# BattVoltageLevelDetector.net
KiCad netlist of a schematic drawn in Altium Designer
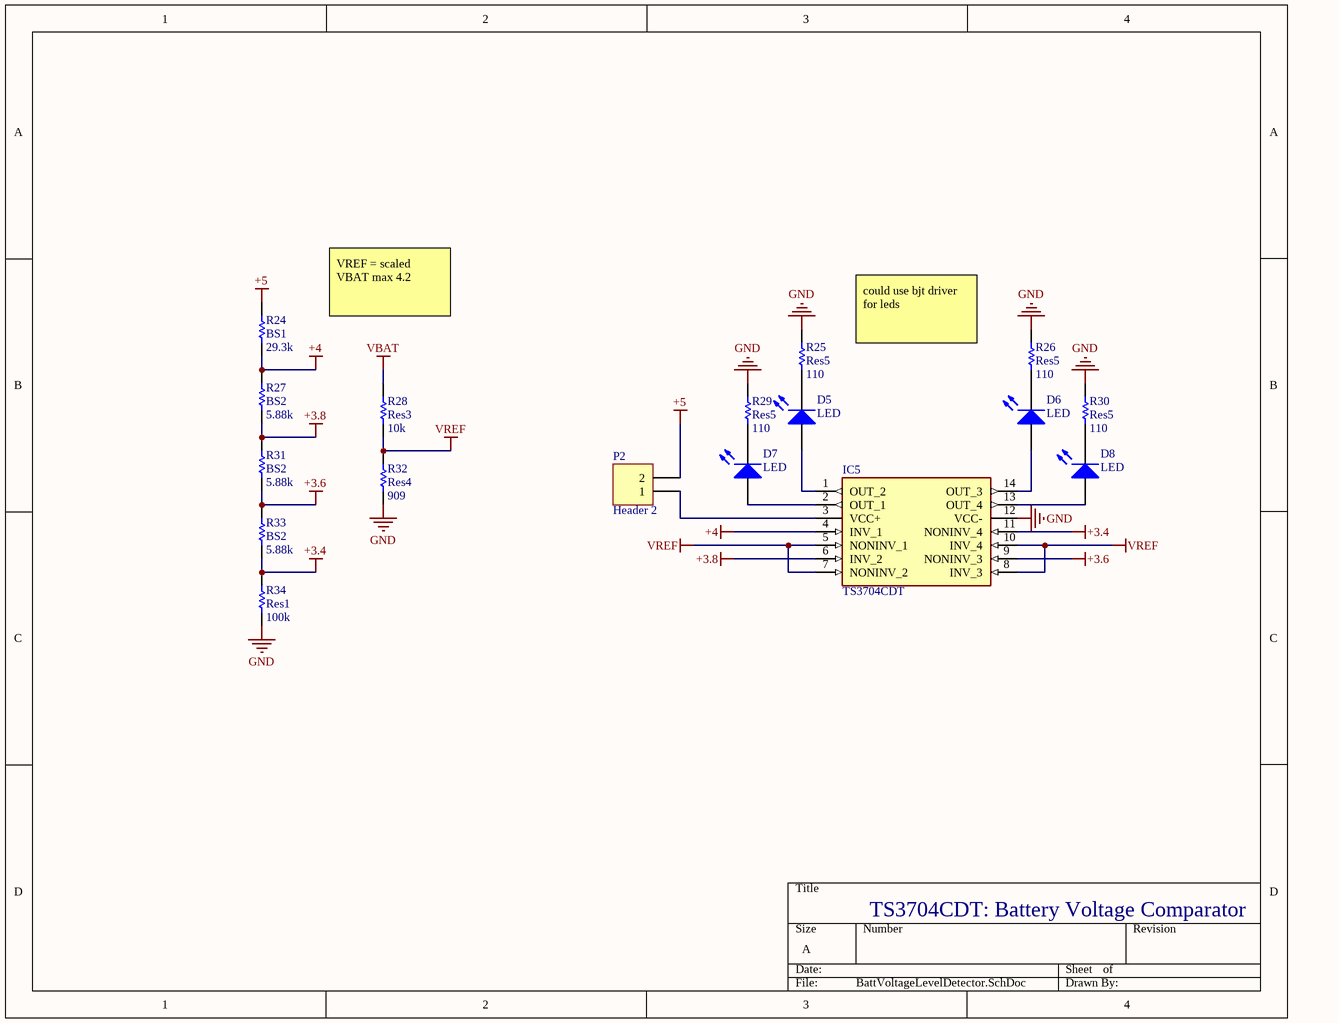
[diagram p0: BattVoltageLevelDetector.SchDoc]

(export (version "E")
  (design (tool "Eeschema 10.0.6"))
  (components
    (comp (ref "D5")
      (value "LED")
      (footprint "0402")
      (description "Typical INFRARED GaAs LED")
      (fields (field (name "PUBLISHER") "Altium Limited"))
      (libsource (lib "Miscellaneous Devices") (part "LED0"))
    )
    (comp (ref "D6")
      (value "LED")
      (footprint "0402")
      (description "Typical INFRARED GaAs LED")
      (fields (field (name "PUBLISHER") "Altium Limited"))
      (libsource (lib "Miscellaneous Devices") (part "LED0"))
    )
    (comp (ref "D7")
      (value "LED")
      (footprint "0402")
      (description "Typical INFRARED GaAs LED")
      (fields (field (name "PUBLISHER") "Altium Limited"))
      (libsource (lib "Miscellaneous Devices") (part "LED0"))
    )
    (comp (ref "D8")
      (value "LED")
      (footprint "0402")
      (description "Typical INFRARED GaAs LED")
      (fields (field (name "PUBLISHER") "Altium Limited"))
      (libsource (lib "Miscellaneous Devices") (part "LED0"))
    )
    (comp (ref "IC5")
      (value "TS3704CDT")
      (footprint "SOIC127P600X175-14N")
      (description "Integrated Circuit")
      (fields (field (name "MOUSER PART NUMBER") "511-TS3704CDT") (field (name "RS PART NUMBER") "8805496P"))
      (libsource (lib "*") (part "TS3704CDT"))
    )
    (comp (ref "P2")
      (value "Header 2")
      (footprint "HDR1X2")
      (description "Header, 2-Pin")
      (fields (field (name "PUBLISHER") "Altium Limited"))
      (libsource (lib "Miscellaneous Connectors") (part "Header 2"))
    )
    (comp (ref "R24")
      (value "BS1")
      (footprint "0402")
      (description "Resistor")
      (fields (field (name "ALTIUM_VALUE") "29.3k") (field (name "PUBLISHER") "Altium Limited"))
      (libsource (lib "Miscellaneous Devices") (part "Res1"))
    )
    (comp (ref "R25")
      (value "Res5")
      (footprint "0402")
      (description "Resistor")
      (fields (field (name "ALTIUM_VALUE") "110") (field (name "PUBLISHER") "Altium Limited"))
      (libsource (lib "Miscellaneous Devices") (part "Res1"))
    )
    (comp (ref "R26")
      (value "Res5")
      (footprint "0402")
      (description "Resistor")
      (fields (field (name "ALTIUM_VALUE") "110") (field (name "PUBLISHER") "Altium Limited"))
      (libsource (lib "Miscellaneous Devices") (part "Res1"))
    )
    (comp (ref "R27")
      (value "BS2")
      (footprint "0402")
      (description "Resistor")
      (fields (field (name "ALTIUM_VALUE") "5.88k") (field (name "PUBLISHER") "Altium Limited"))
      (libsource (lib "Miscellaneous Devices") (part "Res1"))
    )
    (comp (ref "R28")
      (value "Res3")
      (footprint "0402")
      (description "Resistor")
      (fields (field (name "ALTIUM_VALUE") "10k") (field (name "PUBLISHER") "Altium Limited"))
      (libsource (lib "Miscellaneous Devices") (part "Res1"))
    )
    (comp (ref "R29")
      (value "Res5")
      (footprint "0402")
      (description "Resistor")
      (fields (field (name "ALTIUM_VALUE") "110") (field (name "PUBLISHER") "Altium Limited"))
      (libsource (lib "Miscellaneous Devices") (part "Res1"))
    )
    (comp (ref "R30")
      (value "Res5")
      (footprint "0402")
      (description "Resistor")
      (fields (field (name "ALTIUM_VALUE") "110") (field (name "PUBLISHER") "Altium Limited"))
      (libsource (lib "Miscellaneous Devices") (part "Res1"))
    )
    (comp (ref "R31")
      (value "BS2")
      (footprint "0402")
      (description "Resistor")
      (fields (field (name "ALTIUM_VALUE") "5.88k") (field (name "PUBLISHER") "Altium Limited"))
      (libsource (lib "Miscellaneous Devices") (part "Res1"))
    )
    (comp (ref "R32")
      (value "Res4")
      (footprint "0402")
      (description "Resistor")
      (fields (field (name "ALTIUM_VALUE") "909") (field (name "PUBLISHER") "Altium Limited"))
      (libsource (lib "Miscellaneous Devices") (part "Res1"))
    )
    (comp (ref "R33")
      (value "BS2")
      (footprint "0402")
      (description "Resistor")
      (fields (field (name "ALTIUM_VALUE") "5.88k") (field (name "PUBLISHER") "Altium Limited"))
      (libsource (lib "Miscellaneous Devices") (part "Res1"))
    )
    (comp (ref "R34")
      (value "Res1")
      (footprint "0402")
      (description "Resistor")
      (fields (field (name "ALTIUM_VALUE") "100k") (field (name "PUBLISHER") "Altium Limited"))
      (libsource (lib "Miscellaneous Devices") (part "Res1"))
    )
  )
  (nets
    (net (code "1") (name "+3.4") (class "Default")
      (node (ref "IC5") (pin "11") (pinfunction "NONINV_4_11") (pintype "input"))
      (node (ref "R33") (pin "1") (pinfunction "1_1") (pintype "passive"))
      (node (ref "R34") (pin "2") (pinfunction "2_2") (pintype "passive"))
    )
    (net (code "2") (name "+3.6") (class "Default")
      (node (ref "IC5") (pin "9") (pinfunction "NONINV_3_9") (pintype "input"))
      (node (ref "R31") (pin "1") (pinfunction "1_1") (pintype "passive"))
      (node (ref "R33") (pin "2") (pinfunction "2_2") (pintype "passive"))
    )
    (net (code "3") (name "+3.8") (class "Default")
      (node (ref "IC5") (pin "6") (pinfunction "INV_2_6") (pintype "input"))
      (node (ref "R27") (pin "1") (pinfunction "1_1") (pintype "passive"))
      (node (ref "R31") (pin "2") (pinfunction "2_2") (pintype "passive"))
    )
    (net (code "4") (name "+4") (class "Default")
      (node (ref "IC5") (pin "4") (pinfunction "INV_1_4") (pintype "input"))
      (node (ref "R24") (pin "1") (pinfunction "1_1") (pintype "passive"))
      (node (ref "R27") (pin "2") (pinfunction "2_2") (pintype "passive"))
    )
    (net (code "5") (name "+5") (class "Default")
      (node (ref "P2") (pin "2") (pinfunction "2_2") (pintype "passive"))
      (node (ref "R24") (pin "2") (pinfunction "2_2") (pintype "passive"))
    )
    (net (code "6") (name "GND") (class "Default")
      (node (ref "IC5") (pin "12") (pinfunction "VCC-_12") (pintype "power_in"))
      (node (ref "R25") (pin "2") (pinfunction "2_2") (pintype "passive"))
      (node (ref "R26") (pin "2") (pinfunction "2_2") (pintype "passive"))
      (node (ref "R29") (pin "2") (pinfunction "2_2") (pintype "passive"))
      (node (ref "R30") (pin "2") (pinfunction "2_2") (pintype "passive"))
      (node (ref "R32") (pin "1") (pinfunction "1_1") (pintype "passive"))
      (node (ref "R34") (pin "1") (pinfunction "1_1") (pintype "passive"))
    )
    (net (code "7") (name "Net-(D5-A)") (class "Default")
      (node (ref "D5") (pin "1") (pinfunction "A_1") (pintype "passive"))
      (node (ref "IC5") (pin "1") (pinfunction "OUT_2_1") (pintype "output"))
    )
    (net (code "8") (name "Net-(D5-K)") (class "Default")
      (node (ref "D5") (pin "2") (pinfunction "K_2") (pintype "passive"))
      (node (ref "R25") (pin "1") (pinfunction "1_1") (pintype "passive"))
    )
    (net (code "9") (name "Net-(D6-A)") (class "Default")
      (node (ref "D6") (pin "1") (pinfunction "A_1") (pintype "passive"))
      (node (ref "IC5") (pin "14") (pinfunction "OUT_3_14") (pintype "output"))
    )
    (net (code "10") (name "Net-(D6-K)") (class "Default")
      (node (ref "D6") (pin "2") (pinfunction "K_2") (pintype "passive"))
      (node (ref "R26") (pin "1") (pinfunction "1_1") (pintype "passive"))
    )
    (net (code "11") (name "Net-(D7-A)") (class "Default")
      (node (ref "D7") (pin "1") (pinfunction "A_1") (pintype "passive"))
      (node (ref "IC5") (pin "2") (pinfunction "OUT_1_2") (pintype "output"))
    )
    (net (code "12") (name "Net-(D7-K)") (class "Default")
      (node (ref "D7") (pin "2") (pinfunction "K_2") (pintype "passive"))
      (node (ref "R29") (pin "1") (pinfunction "1_1") (pintype "passive"))
    )
    (net (code "13") (name "Net-(D8-A)") (class "Default")
      (node (ref "D8") (pin "1") (pinfunction "A_1") (pintype "passive"))
      (node (ref "IC5") (pin "13") (pinfunction "OUT_4_13") (pintype "output"))
    )
    (net (code "14") (name "Net-(D8-K)") (class "Default")
      (node (ref "D8") (pin "2") (pinfunction "K_2") (pintype "passive"))
      (node (ref "R30") (pin "1") (pinfunction "1_1") (pintype "passive"))
    )
    (net (code "15") (name "Net-(IC5-VCC+)") (class "Default")
      (node (ref "IC5") (pin "3") (pinfunction "VCC+_3") (pintype "power_in"))
      (node (ref "P2") (pin "1") (pinfunction "1_1") (pintype "passive"))
    )
    (net (code "16") (name "VBAT") (class "Default")
      (node (ref "R28") (pin "2") (pinfunction "2_2") (pintype "passive"))
    )
    (net (code "17") (name "VREF") (class "Default")
      (node (ref "IC5") (pin "10") (pinfunction "INV_4_10") (pintype "input"))
      (node (ref "IC5") (pin "5") (pinfunction "NONINV_1_5") (pintype "input"))
      (node (ref "IC5") (pin "7") (pinfunction "NONINV_2_7") (pintype "input"))
      (node (ref "IC5") (pin "8") (pinfunction "INV_3_8") (pintype "input"))
      (node (ref "R28") (pin "1") (pinfunction "1_1") (pintype "passive"))
      (node (ref "R32") (pin "2") (pinfunction "2_2") (pintype "passive"))
    )
  )
)
